# RELAY_BRD_V3.net
KiCad netlist of a schematic drawn in EAGLE
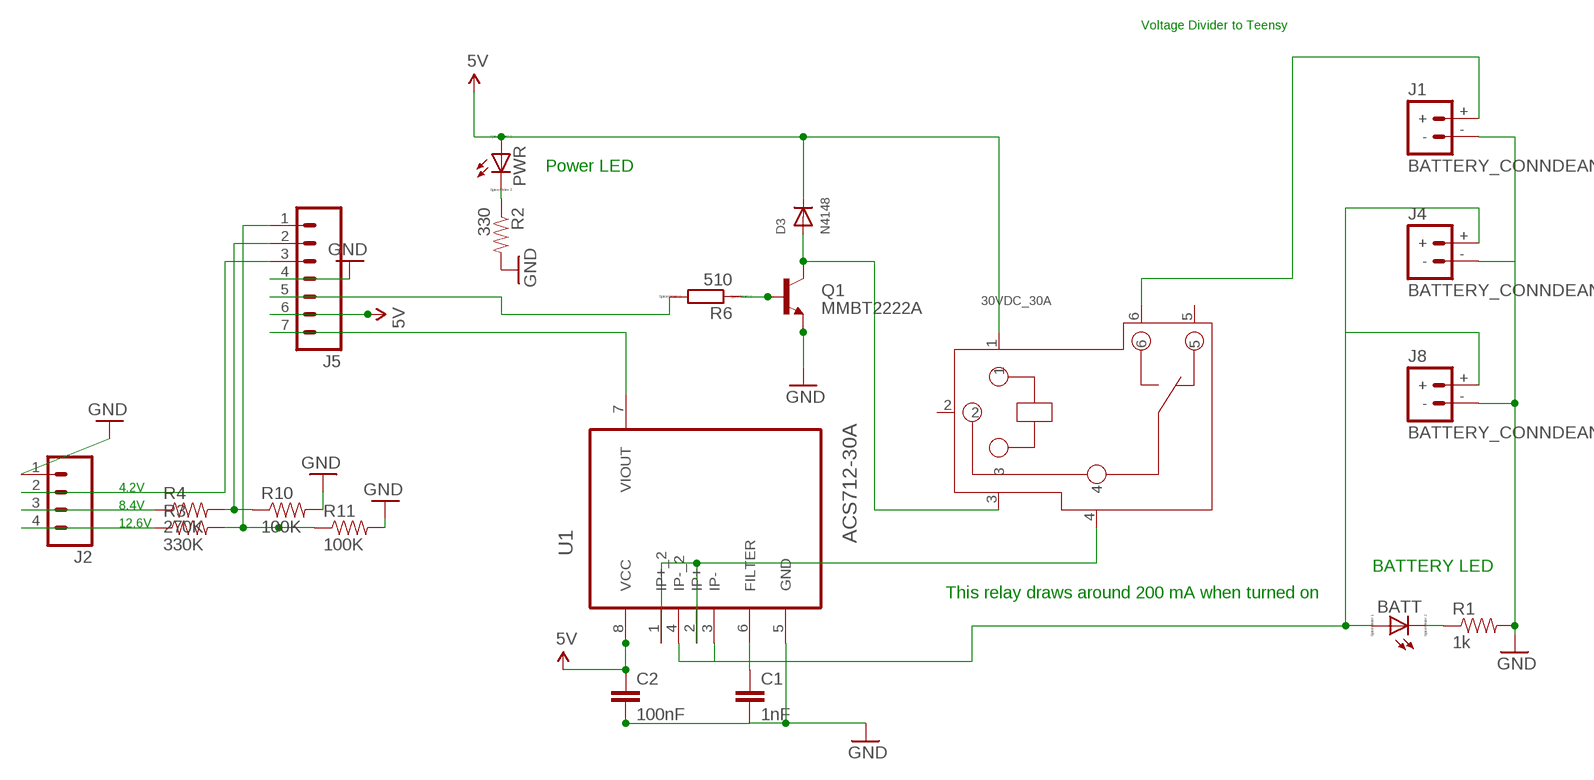
[diagram p0: schematic, sheet 1]

(export (version "E")
  (design (tool "Eeschema 10.0.6"))
  (components
    (comp (ref "30VDC_30A")
      (value "RELAY-SLA-05VDC-SL-C")
      (footprint "eagle-import:6P-19.8H")
      (libsource (lib "eagle-import") (part "RELAY-SLA-05VDC-SL-C"))
    )
    (comp (ref "BATT")
      (value "LED_E")
      (footprint "eagle-import:LED_1206")
      (libsource (lib "eagle-import") (part "LED_E"))
    )
    (comp (ref "C1")
      (value "1nF")
      (footprint "eagle-import:1206")
      (libsource (lib "eagle-import") (part "CAP1206"))
    )
    (comp (ref "C2")
      (value "100nF")
      (footprint "eagle-import:1206")
      (libsource (lib "eagle-import") (part "CAP1206"))
    )
    (comp (ref "D3")
      (value "N4148")
      (footprint "eagle-import:DO-1N4148")
      (libsource (lib "eagle-import") (part "DIODEDO-1N4148"))
    )
    (comp (ref "J1")
      (value "BATTERY_CONNDEANS")
      (footprint "eagle-import:DEANS")
      (libsource (lib "eagle-import") (part "BATTERY_CONNDEANS"))
    )
    (comp (ref "J2")
      (value "M04POLAR")
      (footprint "eagle-import:MOLEX-1X4")
      (libsource (lib "eagle-import") (part "M04POLAR"))
    )
    (comp (ref "J4")
      (value "BATTERY_CONNDEANS")
      (footprint "eagle-import:DEANS")
      (libsource (lib "eagle-import") (part "BATTERY_CONNDEANS"))
    )
    (comp (ref "J5")
      (value "M07LOCK_LONGPADS")
      (footprint "eagle-import:1X07_LOCK_LONGPADS")
      (libsource (lib "eagle-import") (part "M07LOCK_LONGPADS"))
    )
    (comp (ref "J8")
      (value "BATTERY_CONNDEANS")
      (footprint "eagle-import:DEANS")
      (libsource (lib "eagle-import") (part "BATTERY_CONNDEANS"))
    )
    (comp (ref "PWR")
      (value "LED_E")
      (footprint "eagle-import:LED_1206")
      (libsource (lib "eagle-import") (part "LED_E"))
    )
    (comp (ref "Q1")
      (value "MMBT2222A")
      (footprint "eagle-import:SOT23-3")
      (libsource (lib "eagle-import") (part "TRANSISTOR_NPNMMBT2222A"))
    )
    (comp (ref "R1")
      (value "1k")
      (footprint "eagle-import:1206")
      (libsource (lib "eagle-import") (part "RESISTOR1206"))
    )
    (comp (ref "R2")
      (value "330")
      (footprint "eagle-import:1206")
      (libsource (lib "eagle-import") (part "RESISTOR1206"))
    )
    (comp (ref "R3")
      (value "330K")
      (footprint "eagle-import:1206")
      (libsource (lib "eagle-import") (part "RESISTOR1206"))
    )
    (comp (ref "R4")
      (value "270K")
      (footprint "eagle-import:1206")
      (libsource (lib "eagle-import") (part "RESISTOR1206"))
    )
    (comp (ref "R6")
      (value "510")
      (footprint "eagle-import:R1206")
      (libsource (lib "eagle-import") (part "RR1206"))
    )
    (comp (ref "R10")
      (value "100K")
      (footprint "eagle-import:1206")
      (libsource (lib "eagle-import") (part "RESISTOR1206"))
    )
    (comp (ref "R11")
      (value "100K")
      (footprint "eagle-import:1206")
      (libsource (lib "eagle-import") (part "RESISTOR1206"))
    )
    (comp (ref "U1")
      (value "ACS712-30A")
      (footprint "eagle-import:SOIC127P600X175-8N")
      (fields (field (name "MPN") "ACS712ELCTR-20A-T"))
      (libsource (lib "eagle-import") (part "ACS712ELCTR-20A-T"))
    )
  )
  (nets
    (net (code "1") (name "5V") (class "Default")
      (node (ref "30VDC_30A") (pin "1") (pinfunction "1_1") (pintype "bidirectional"))
      (node (ref "C2") (pin "1") (pinfunction "1_1") (pintype "passive"))
      (node (ref "D3") (pin "C") (pinfunction "C_C") (pintype "passive"))
      (node (ref "J5") (pin "6") (pinfunction "6_6") (pintype "passive"))
      (node (ref "PWR") (pin "A") (pinfunction "A_A") (pintype "passive"))
      (node (ref "U1") (pin "8") (pinfunction "VCC_8") (pintype "power_in"))
    )
    (net (code "2") (name "GND") (class "Default")
      (node (ref "C1") (pin "2") (pinfunction "2_2") (pintype "passive"))
      (node (ref "C2") (pin "2") (pinfunction "2_2") (pintype "passive"))
      (node (ref "J1") (pin "-") (pinfunction "-_-") (pintype "passive"))
      (node (ref "J2") (pin "1") (pinfunction "1_1") (pintype "passive"))
      (node (ref "J4") (pin "-") (pinfunction "-_-") (pintype "passive"))
      (node (ref "J5") (pin "4") (pinfunction "4_4") (pintype "passive"))
      (node (ref "J8") (pin "-") (pinfunction "-_-") (pintype "passive"))
      (node (ref "Q1") (pin "2") (pinfunction "E_2") (pintype "passive"))
      (node (ref "R1") (pin "2") (pinfunction "2_2") (pintype "passive"))
      (node (ref "R10") (pin "2") (pinfunction "2_2") (pintype "passive"))
      (node (ref "R11") (pin "2") (pinfunction "2_2") (pintype "passive"))
      (node (ref "R2") (pin "2") (pinfunction "2_2") (pintype "passive"))
      (node (ref "U1") (pin "5") (pinfunction "GND_5") (pintype "passive"))
    )
    (net (code "3") (name "Net-(30VDC_30A-Pad6)") (class "Default")
      (node (ref "30VDC_30A") (pin "6") (pinfunction "6_6") (pintype "bidirectional"))
      (node (ref "J1") (pin "+") (pinfunction "+_+") (pintype "passive"))
    )
    (net (code "4") (name "Net-(BATT-PadC)") (class "Default")
      (node (ref "BATT") (pin "C") (pinfunction "C_C") (pintype "passive"))
      (node (ref "R1") (pin "1") (pinfunction "1_1") (pintype "passive"))
    )
    (net (code "5") (name "Net-(J2-Pad2)") (class "Default")
      (node (ref "J2") (pin "2") (pinfunction "2_2") (pintype "passive"))
      (node (ref "J5") (pin "3") (pinfunction "3_3") (pintype "passive"))
    )
    (net (code "6") (name "Net-(J2-Pad3)") (class "Default")
      (node (ref "J2") (pin "3") (pinfunction "3_3") (pintype "passive"))
      (node (ref "R4") (pin "1") (pinfunction "1_1") (pintype "passive"))
    )
    (net (code "7") (name "Net-(J2-Pad4)") (class "Default")
      (node (ref "J2") (pin "4") (pinfunction "4_4") (pintype "passive"))
      (node (ref "R3") (pin "1") (pinfunction "1_1") (pintype "passive"))
    )
    (net (code "8") (name "Net-(J5-Pad1)") (class "Default")
      (node (ref "J5") (pin "1") (pinfunction "1_1") (pintype "passive"))
      (node (ref "R11") (pin "1") (pinfunction "1_1") (pintype "passive"))
      (node (ref "R3") (pin "2") (pinfunction "2_2") (pintype "passive"))
    )
    (net (code "9") (name "Net-(J5-Pad2)") (class "Default")
      (node (ref "J5") (pin "2") (pinfunction "2_2") (pintype "passive"))
      (node (ref "R10") (pin "1") (pinfunction "1_1") (pintype "passive"))
      (node (ref "R4") (pin "2") (pinfunction "2_2") (pintype "passive"))
    )
    (net (code "10") (name "Net-(J5-Pad5)") (class "Default")
      (node (ref "J5") (pin "5") (pinfunction "5_5") (pintype "passive"))
      (node (ref "R6") (pin "2") (pinfunction "2_2") (pintype "passive"))
    )
    (net (code "11") (name "Net-(PWR-PadC)") (class "Default")
      (node (ref "PWR") (pin "C") (pinfunction "C_C") (pintype "passive"))
      (node (ref "R2") (pin "1") (pinfunction "1_1") (pintype "passive"))
    )
    (net (code "12") (name "Net-(Q1-B)") (class "Default")
      (node (ref "Q1") (pin "1") (pinfunction "B_1") (pintype "passive"))
      (node (ref "R6") (pin "1") (pinfunction "1_1") (pintype "passive"))
    )
    (net (code "13") (name "Net-(Q1-C)") (class "Default")
      (node (ref "30VDC_30A") (pin "3") (pinfunction "3_3") (pintype "bidirectional"))
      (node (ref "D3") (pin "A") (pinfunction "A_A") (pintype "passive"))
      (node (ref "Q1") (pin "3") (pinfunction "C_3") (pintype "passive"))
    )
    (net (code "14") (name "Net-(U1-FILTER)") (class "Default")
      (node (ref "C1") (pin "1") (pinfunction "1_1") (pintype "passive"))
      (node (ref "U1") (pin "6") (pinfunction "FILTER_6") (pintype "input"))
    )
    (net (code "15") (name "Net-(U1-IP+)") (class "Default")
      (node (ref "30VDC_30A") (pin "4") (pinfunction "4_4") (pintype "bidirectional"))
      (node (ref "U1") (pin "1") (pinfunction "IP+_2_1") (pintype "input"))
      (node (ref "U1") (pin "2") (pinfunction "IP+_2") (pintype "input"))
    )
    (net (code "16") (name "Net-(U1-IP-)") (class "Default")
      (node (ref "BATT") (pin "A") (pinfunction "A_A") (pintype "passive"))
      (node (ref "J4") (pin "+") (pinfunction "+_+") (pintype "passive"))
      (node (ref "J8") (pin "+") (pinfunction "+_+") (pintype "passive"))
      (node (ref "U1") (pin "3") (pinfunction "IP-_3") (pintype "input"))
      (node (ref "U1") (pin "4") (pinfunction "IP-_2_4") (pintype "input"))
    )
    (net (code "17") (name "Net-(U1-VIOUT)") (class "Default")
      (node (ref "J5") (pin "7") (pinfunction "7_7") (pintype "passive"))
      (node (ref "U1") (pin "7") (pinfunction "VIOUT_7") (pintype "output"))
    )
    (net (code "18") (name "unconnected-(30VDC_30A-Pad2)") (class "Default")
      (node (ref "30VDC_30A") (pin "2") (pinfunction "2_2") (pintype "bidirectional"))
    )
    (net (code "19") (name "unconnected-(30VDC_30A-Pad5)") (class "Default")
      (node (ref "30VDC_30A") (pin "5") (pinfunction "5_5") (pintype "bidirectional"))
    )
  )
)
